# sensor1.net
KiCad netlist of a schematic drawn in EAGLE
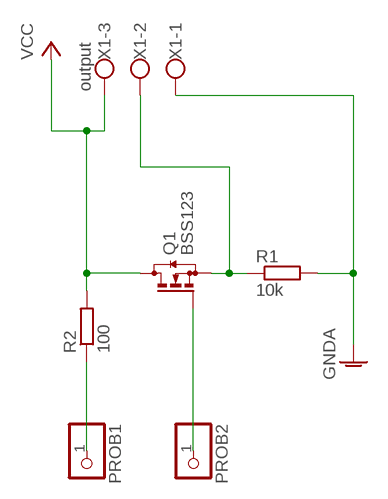
[diagram p0: schematic, sheet 1]

(export (version "E")
  (design (tool "Eeschema 10.0.6"))
  (components
    (comp (ref "PROB1")
      (value "PINHD-1X1")
      (footprint "eagle-import:1X01")
      (libsource (lib "eagle-import") (part "PINHD-1X1"))
    )
    (comp (ref "PROB2")
      (value "PINHD-1X1")
      (footprint "eagle-import:1X01")
      (libsource (lib "eagle-import") (part "PINHD-1X1"))
    )
    (comp (ref "Q1")
      (value "BSS123")
      (footprint "eagle-import:SOT23")
      (libsource (lib "eagle-import") (part "BSS123"))
    )
    (comp (ref "R1")
      (value "10k")
      (footprint "eagle-import:R1206W")
      (libsource (lib "eagle-import") (part "R-EU_R1206W"))
    )
    (comp (ref "R2")
      (value "100")
      (footprint "eagle-import:R1206W")
      (libsource (lib "eagle-import") (part "R-EU_R1206W"))
    )
    (comp (ref "X1")
      (value "output")
      (footprint "eagle-import:W237-103")
      (fields (field (name "MPN") "237-103"))
      (libsource (lib "eagle-import") (part "W237-103"))
    )
  )
  (nets
    (net (code "1") (name "GNDA") (class "Default")
      (node (ref "R1") (pin "2") (pinfunction "2_2") (pintype "passive"))
      (node (ref "X1") (pin "1") (pinfunction "KL_1") (pintype "passive"))
    )
    (net (code "2") (name "Net-(PROB1-Pad1)") (class "Default")
      (node (ref "PROB1") (pin "1") (pinfunction "1_1") (pintype "passive"))
      (node (ref "R2") (pin "1") (pinfunction "1_1") (pintype "passive"))
    )
    (net (code "3") (name "Net-(Q1-G)") (class "Default")
      (node (ref "PROB2") (pin "1") (pinfunction "1_1") (pintype "passive"))
      (node (ref "Q1") (pin "1") (pinfunction "G_1") (pintype "passive"))
    )
    (net (code "4") (name "Net-(Q1-S)") (class "Default")
      (node (ref "Q1") (pin "2") (pinfunction "S_2") (pintype "passive"))
      (node (ref "R1") (pin "1") (pinfunction "1_1") (pintype "passive"))
      (node (ref "X1") (pin "2") (pinfunction "KL_2") (pintype "passive"))
    )
    (net (code "5") (name "VCC") (class "Default")
      (node (ref "Q1") (pin "3") (pinfunction "D_3") (pintype "passive"))
      (node (ref "R2") (pin "2") (pinfunction "2_2") (pintype "passive"))
      (node (ref "X1") (pin "3") (pinfunction "KL_3") (pintype "passive"))
    )
  )
)
